# schematics.net
KiCad netlist of a schematic drawn in EAGLE
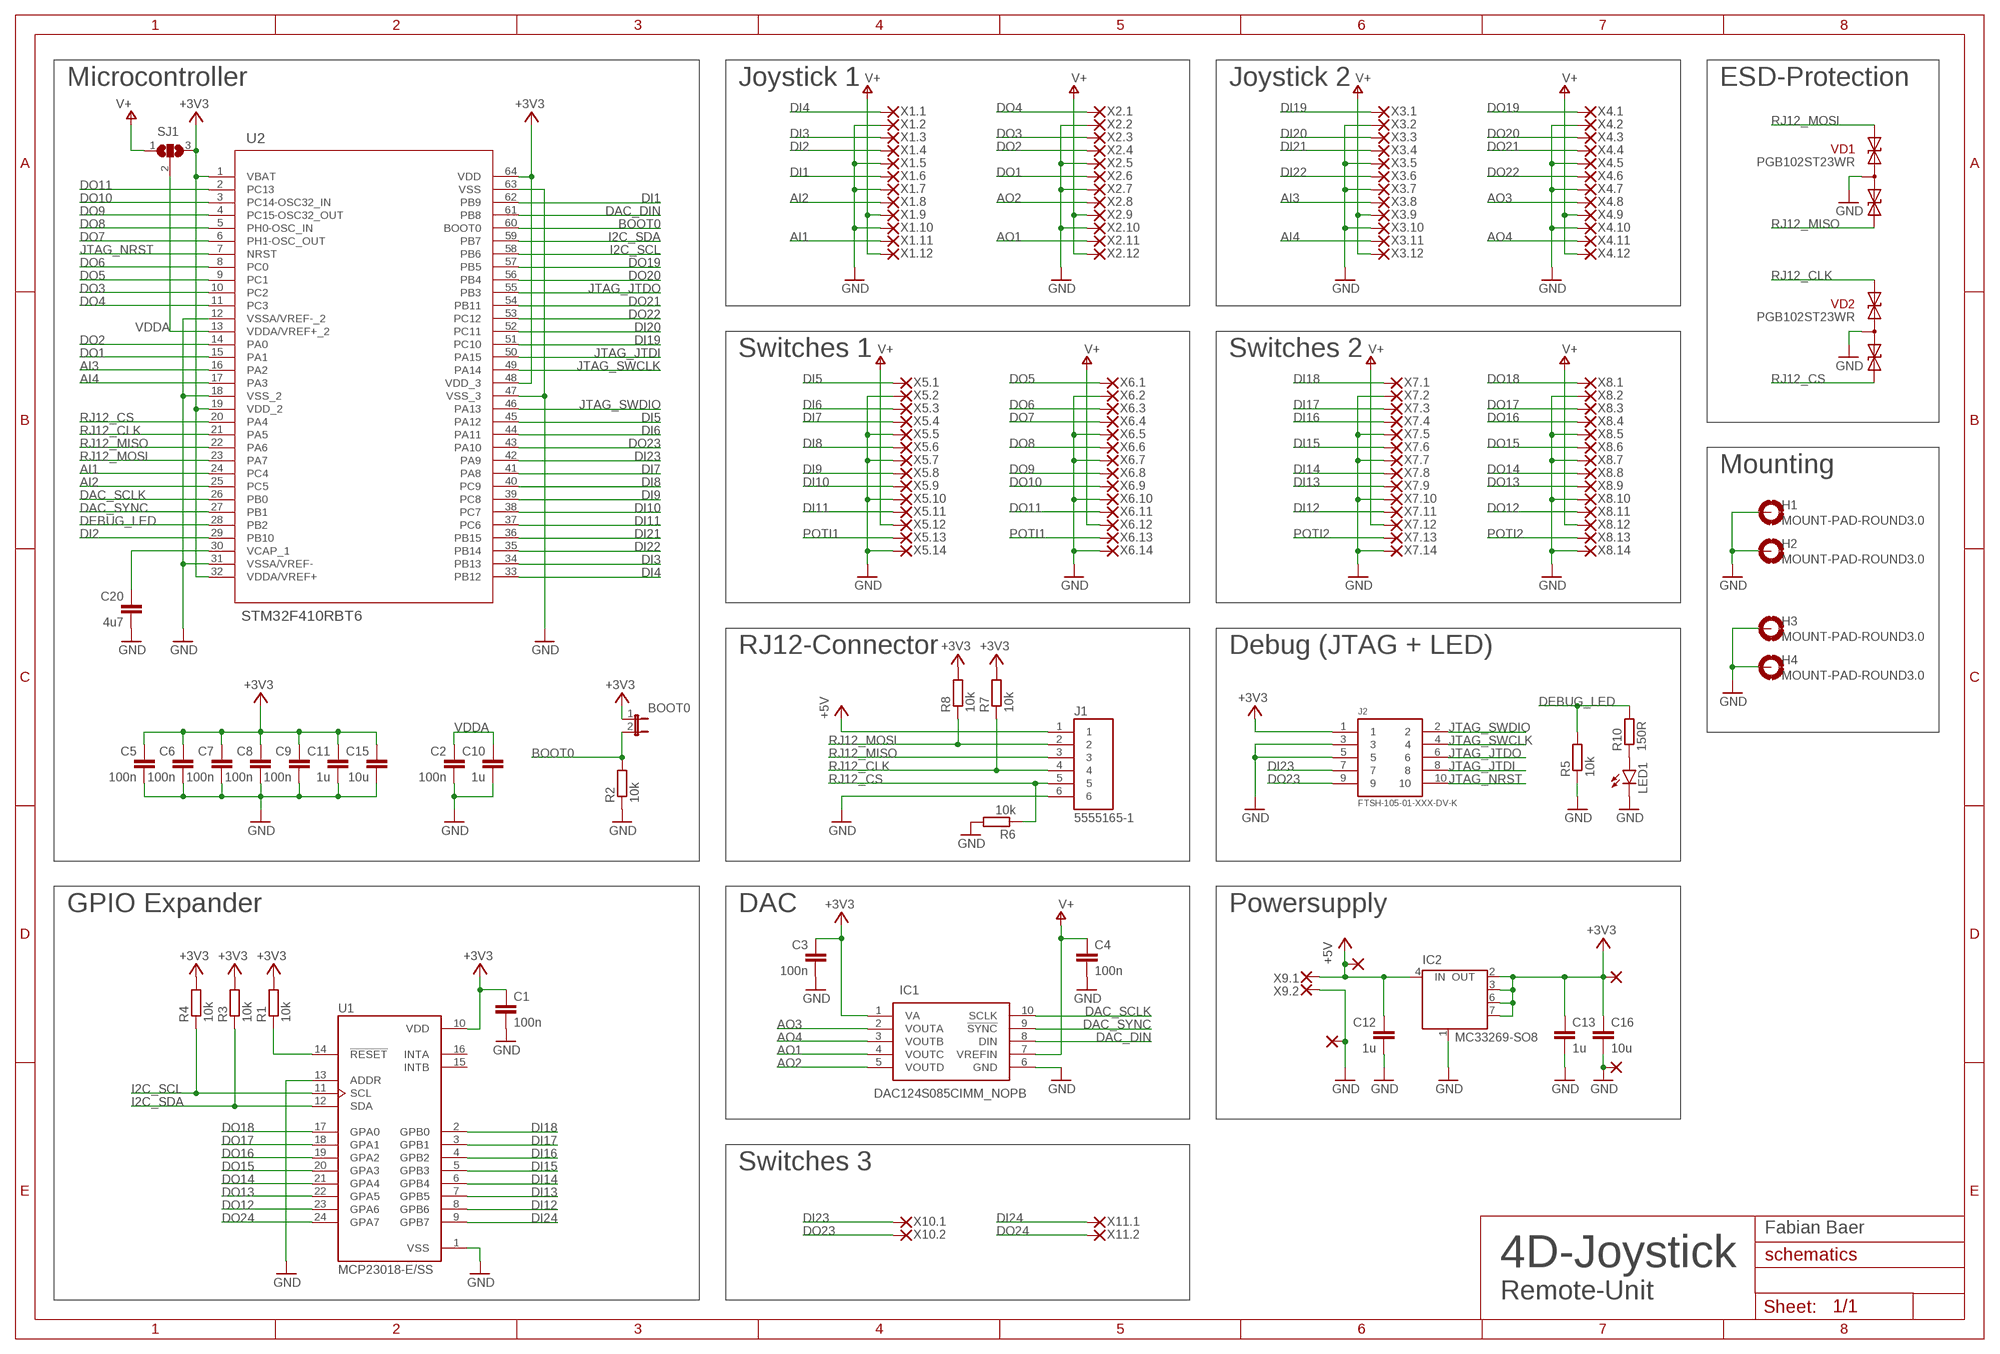
[diagram p0: schematic, sheet 1]

(export (version "E")
  (design (tool "Eeschema 10.0.6"))
  (components
    (comp (ref "BOOT0")
      (value "JP1E")
      (footprint "eagle-import:JP1")
      (libsource (lib "eagle-import") (part "JP1E"))
    )
    (comp (ref "C1")
      (value "100n")
      (footprint "eagle-import:C0603")
      (libsource (lib "eagle-import") (part "C-EUC0603"))
    )
    (comp (ref "C2")
      (value "100n")
      (footprint "eagle-import:C0603")
      (libsource (lib "eagle-import") (part "C-EUC0603"))
    )
    (comp (ref "C3")
      (value "100n")
      (footprint "eagle-import:C0603")
      (libsource (lib "eagle-import") (part "C-EUC0603"))
    )
    (comp (ref "C4")
      (value "100n")
      (footprint "eagle-import:C0603")
      (libsource (lib "eagle-import") (part "C-EUC0603"))
    )
    (comp (ref "C5")
      (value "100n")
      (footprint "eagle-import:C0603")
      (libsource (lib "eagle-import") (part "C-EUC0603"))
    )
    (comp (ref "C6")
      (value "100n")
      (footprint "eagle-import:C0603")
      (libsource (lib "eagle-import") (part "C-EUC0603"))
    )
    (comp (ref "C7")
      (value "100n")
      (footprint "eagle-import:C0603")
      (libsource (lib "eagle-import") (part "C-EUC0603"))
    )
    (comp (ref "C8")
      (value "100n")
      (footprint "eagle-import:C0603")
      (libsource (lib "eagle-import") (part "C-EUC0603"))
    )
    (comp (ref "C9")
      (value "100n")
      (footprint "eagle-import:C0603")
      (libsource (lib "eagle-import") (part "C-EUC0603"))
    )
    (comp (ref "C10")
      (value "1u")
      (footprint "eagle-import:C0603")
      (libsource (lib "eagle-import") (part "C-EUC0603"))
    )
    (comp (ref "C11")
      (value "1u")
      (footprint "eagle-import:C0603")
      (libsource (lib "eagle-import") (part "C-EUC0603"))
    )
    (comp (ref "C12")
      (value "1u")
      (footprint "eagle-import:C0603")
      (libsource (lib "eagle-import") (part "C-EUC0603"))
    )
    (comp (ref "C13")
      (value "1u")
      (footprint "eagle-import:C0603")
      (libsource (lib "eagle-import") (part "C-EUC0603"))
    )
    (comp (ref "C15")
      (value "10u")
      (footprint "eagle-import:C0603")
      (libsource (lib "eagle-import") (part "C-EUC0603"))
    )
    (comp (ref "C16")
      (value "10u")
      (footprint "eagle-import:C0603")
      (libsource (lib "eagle-import") (part "C-EUC0603"))
    )
    (comp (ref "C20")
      (value "4u7")
      (footprint "eagle-import:C0603")
      (libsource (lib "eagle-import") (part "C-EUC0603"))
    )
    (comp (ref "H1")
      (value "MOUNT-PAD-ROUND3.0")
      (footprint "eagle-import:3,0-PAD")
      (libsource (lib "eagle-import") (part "MOUNT-PAD-ROUND3.0"))
    )
    (comp (ref "H2")
      (value "MOUNT-PAD-ROUND3.0")
      (footprint "eagle-import:3,0-PAD")
      (libsource (lib "eagle-import") (part "MOUNT-PAD-ROUND3.0"))
    )
    (comp (ref "H3")
      (value "MOUNT-PAD-ROUND3.0")
      (footprint "eagle-import:3,0-PAD")
      (libsource (lib "eagle-import") (part "MOUNT-PAD-ROUND3.0"))
    )
    (comp (ref "H4")
      (value "MOUNT-PAD-ROUND3.0")
      (footprint "eagle-import:3,0-PAD")
      (libsource (lib "eagle-import") (part "MOUNT-PAD-ROUND3.0"))
    )
    (comp (ref "IC1")
      (value "DAC124S085CIMM_NOPB")
      (footprint "eagle-import:SOP50P490X110-10N")
      (fields
        (field (name "MANUFACTURER_PART_NUMBER") "DAC124S085CIMM/NOPB")
        (field (name "MOUSER_PART_NUMBER") "926-DAC124S085CIMMNO")
        (field (name "RS_PART_NUMBER") "6512026P")
      )
      (libsource (lib "eagle-import") (part "DAC124S085CIMM_NOPB"))
    )
    (comp (ref "IC2")
      (value "MC33269-SO8")
      (footprint "eagle-import:SO08")
      (libsource (lib "eagle-import") (part "MC33269-SO8"))
    )
    (comp (ref "J1")
      (value "5555165-1")
      (footprint "eagle-import:TE_5555165-1")
      (fields (field (name "MF") "TE Connectivity"))
      (libsource (lib "eagle-import") (part "5555165-1"))
    )
    (comp (ref "J2")
      (value "FTSH-105-01-XXX-DV-K")
      (footprint "eagle-import:FTSH-105-01-XXX-DV-K")
      (libsource (lib "eagle-import") (part "FTSH-105-01-XXX-DV-K"))
    )
    (comp (ref "LED1")
      (value "LEDSML0603")
      (footprint "eagle-import:SML0603")
      (libsource (lib "eagle-import") (part "LEDSML0603"))
    )
    (comp (ref "R1")
      (value "10k")
      (footprint "eagle-import:R0603")
      (libsource (lib "eagle-import") (part "R-EU_R0603"))
    )
    (comp (ref "R2")
      (value "10k")
      (footprint "eagle-import:R0603")
      (libsource (lib "eagle-import") (part "R-EU_R0603"))
    )
    (comp (ref "R3")
      (value "10k")
      (footprint "eagle-import:R0603")
      (libsource (lib "eagle-import") (part "R-EU_R0603"))
    )
    (comp (ref "R4")
      (value "10k")
      (footprint "eagle-import:R0603")
      (libsource (lib "eagle-import") (part "R-EU_R0603"))
    )
    (comp (ref "R5")
      (value "10k")
      (footprint "eagle-import:R0603")
      (libsource (lib "eagle-import") (part "R-EU_R0603"))
    )
    (comp (ref "R6")
      (value "10k")
      (footprint "eagle-import:R0603")
      (libsource (lib "eagle-import") (part "R-EU_R0603"))
    )
    (comp (ref "R7")
      (value "10k")
      (footprint "eagle-import:R0603")
      (libsource (lib "eagle-import") (part "R-EU_R0603"))
    )
    (comp (ref "R8")
      (value "10k")
      (footprint "eagle-import:R0603")
      (libsource (lib "eagle-import") (part "R-EU_R0603"))
    )
    (comp (ref "R10")
      (value "150R")
      (footprint "eagle-import:R0603")
      (libsource (lib "eagle-import") (part "R-EU_R0603"))
    )
    (comp (ref "SJ1")
      (value "SJ2W")
      (footprint "eagle-import:SJ_2")
      (libsource (lib "eagle-import") (part "SJ2W"))
    )
    (comp (ref "U1")
      (value "MCP23018-E/SS")
      (footprint "eagle-import:SOP65P780X200-24N")
      (fields (field (name "MF") "Microchip"))
      (libsource (lib "eagle-import") (part "MCP23018-E/SS"))
    )
    (comp (ref "U2")
      (value "STM32F410RBT6")
      (footprint "eagle-import:LQFP64-10X10MM")
      (fields (field (name "MANUFACTURER_PART_NUMBER") "stm32f410r3"))
      (libsource (lib "eagle-import") (part "STM32F410RBT6"))
    )
    (comp (ref "VD1")
      (value "PGB102ST23WR")
      (footprint "eagle-import:SOT23")
      (libsource (lib "eagle-import") (part "PGB102ST23WR"))
    )
    (comp (ref "VD2")
      (value "PGB102ST23WR")
      (footprint "eagle-import:SOT23")
      (libsource (lib "eagle-import") (part "PGB102ST23WR"))
    )
    (comp (ref "X1.1")
      (value "WIREPAD1,6/0,9")
      (footprint "eagle-import:1,6_0,9")
      (libsource (lib "eagle-import") (part "WIREPAD1,6/0,9"))
    )
    (comp (ref "X1.2")
      (value "WIREPAD1,6/0,9")
      (footprint "eagle-import:1,6_0,9")
      (libsource (lib "eagle-import") (part "WIREPAD1,6/0,9"))
    )
    (comp (ref "X1.3")
      (value "WIREPAD1,6/0,9")
      (footprint "eagle-import:1,6_0,9")
      (libsource (lib "eagle-import") (part "WIREPAD1,6/0,9"))
    )
    (comp (ref "X1.4")
      (value "WIREPAD1,6/0,9")
      (footprint "eagle-import:1,6_0,9")
      (libsource (lib "eagle-import") (part "WIREPAD1,6/0,9"))
    )
    (comp (ref "X1.5")
      (value "WIREPAD1,6/0,9")
      (footprint "eagle-import:1,6_0,9")
      (libsource (lib "eagle-import") (part "WIREPAD1,6/0,9"))
    )
    (comp (ref "X1.6")
      (value "WIREPAD1,6/0,9")
      (footprint "eagle-import:1,6_0,9")
      (libsource (lib "eagle-import") (part "WIREPAD1,6/0,9"))
    )
    (comp (ref "X1.7")
      (value "WIREPAD1,6/0,9")
      (footprint "eagle-import:1,6_0,9")
      (libsource (lib "eagle-import") (part "WIREPAD1,6/0,9"))
    )
    (comp (ref "X1.8")
      (value "WIREPAD1,6/0,9")
      (footprint "eagle-import:1,6_0,9")
      (libsource (lib "eagle-import") (part "WIREPAD1,6/0,9"))
    )
    (comp (ref "X1.9")
      (value "WIREPAD1,6/0,9")
      (footprint "eagle-import:1,6_0,9")
      (libsource (lib "eagle-import") (part "WIREPAD1,6/0,9"))
    )
    (comp (ref "X1.10")
      (value "WIREPAD1,6/0,9")
      (footprint "eagle-import:1,6_0,9")
      (libsource (lib "eagle-import") (part "WIREPAD1,6/0,9"))
    )
    (comp (ref "X1.11")
      (value "WIREPAD1,6/0,9")
      (footprint "eagle-import:1,6_0,9")
      (libsource (lib "eagle-import") (part "WIREPAD1,6/0,9"))
    )
    (comp (ref "X1.12")
      (value "WIREPAD1,6/0,9")
      (footprint "eagle-import:1,6_0,9")
      (libsource (lib "eagle-import") (part "WIREPAD1,6/0,9"))
    )
    (comp (ref "X2.1")
      (value "WIREPAD1,6/0,9")
      (footprint "eagle-import:1,6_0,9")
      (libsource (lib "eagle-import") (part "WIREPAD1,6/0,9"))
    )
    (comp (ref "X2.2")
      (value "WIREPAD1,6/0,9")
      (footprint "eagle-import:1,6_0,9")
      (libsource (lib "eagle-import") (part "WIREPAD1,6/0,9"))
    )
    (comp (ref "X2.3")
      (value "WIREPAD1,6/0,9")
      (footprint "eagle-import:1,6_0,9")
      (libsource (lib "eagle-import") (part "WIREPAD1,6/0,9"))
    )
    (comp (ref "X2.4")
      (value "WIREPAD1,6/0,9")
      (footprint "eagle-import:1,6_0,9")
      (libsource (lib "eagle-import") (part "WIREPAD1,6/0,9"))
    )
    (comp (ref "X2.5")
      (value "WIREPAD1,6/0,9")
      (footprint "eagle-import:1,6_0,9")
      (libsource (lib "eagle-import") (part "WIREPAD1,6/0,9"))
    )
    (comp (ref "X2.6")
      (value "WIREPAD1,6/0,9")
      (footprint "eagle-import:1,6_0,9")
      (libsource (lib "eagle-import") (part "WIREPAD1,6/0,9"))
    )
    (comp (ref "X2.7")
      (value "WIREPAD1,6/0,9")
      (footprint "eagle-import:1,6_0,9")
      (libsource (lib "eagle-import") (part "WIREPAD1,6/0,9"))
    )
    (comp (ref "X2.8")
      (value "WIREPAD1,6/0,9")
      (footprint "eagle-import:1,6_0,9")
      (libsource (lib "eagle-import") (part "WIREPAD1,6/0,9"))
    )
    (comp (ref "X2.9")
      (value "WIREPAD1,6/0,9")
      (footprint "eagle-import:1,6_0,9")
      (libsource (lib "eagle-import") (part "WIREPAD1,6/0,9"))
    )
    (comp (ref "X2.10")
      (value "WIREPAD1,6/0,9")
      (footprint "eagle-import:1,6_0,9")
      (libsource (lib "eagle-import") (part "WIREPAD1,6/0,9"))
    )
    (comp (ref "X2.11")
      (value "WIREPAD1,6/0,9")
      (footprint "eagle-import:1,6_0,9")
      (libsource (lib "eagle-import") (part "WIREPAD1,6/0,9"))
    )
    (comp (ref "X2.12")
      (value "WIREPAD1,6/0,9")
      (footprint "eagle-import:1,6_0,9")
      (libsource (lib "eagle-import") (part "WIREPAD1,6/0,9"))
    )
    (comp (ref "X3.1")
      (value "WIREPAD1,6/0,9")
      (footprint "eagle-import:1,6_0,9")
      (libsource (lib "eagle-import") (part "WIREPAD1,6/0,9"))
    )
    (comp (ref "X3.2")
      (value "WIREPAD1,6/0,9")
      (footprint "eagle-import:1,6_0,9")
      (libsource (lib "eagle-import") (part "WIREPAD1,6/0,9"))
    )
    (comp (ref "X3.3")
      (value "WIREPAD1,6/0,9")
      (footprint "eagle-import:1,6_0,9")
      (libsource (lib "eagle-import") (part "WIREPAD1,6/0,9"))
    )
    (comp (ref "X3.4")
      (value "WIREPAD1,6/0,9")
      (footprint "eagle-import:1,6_0,9")
      (libsource (lib "eagle-import") (part "WIREPAD1,6/0,9"))
    )
    (comp (ref "X3.5")
      (value "WIREPAD1,6/0,9")
      (footprint "eagle-import:1,6_0,9")
      (libsource (lib "eagle-import") (part "WIREPAD1,6/0,9"))
    )
    (comp (ref "X3.6")
      (value "WIREPAD1,6/0,9")
      (footprint "eagle-import:1,6_0,9")
      (libsource (lib "eagle-import") (part "WIREPAD1,6/0,9"))
    )
    (comp (ref "X3.7")
      (value "WIREPAD1,6/0,9")
      (footprint "eagle-import:1,6_0,9")
      (libsource (lib "eagle-import") (part "WIREPAD1,6/0,9"))
    )
    (comp (ref "X3.8")
      (value "WIREPAD1,6/0,9")
      (footprint "eagle-import:1,6_0,9")
      (libsource (lib "eagle-import") (part "WIREPAD1,6/0,9"))
    )
    (comp (ref "X3.9")
      (value "WIREPAD1,6/0,9")
      (footprint "eagle-import:1,6_0,9")
      (libsource (lib "eagle-import") (part "WIREPAD1,6/0,9"))
    )
    (comp (ref "X3.10")
      (value "WIREPAD1,6/0,9")
      (footprint "eagle-import:1,6_0,9")
      (libsource (lib "eagle-import") (part "WIREPAD1,6/0,9"))
    )
    (comp (ref "X3.11")
      (value "WIREPAD1,6/0,9")
      (footprint "eagle-import:1,6_0,9")
      (libsource (lib "eagle-import") (part "WIREPAD1,6/0,9"))
    )
    (comp (ref "X3.12")
      (value "WIREPAD1,6/0,9")
      (footprint "eagle-import:1,6_0,9")
      (libsource (lib "eagle-import") (part "WIREPAD1,6/0,9"))
    )
    (comp (ref "X4.1")
      (value "WIREPAD1,6/0,9")
      (footprint "eagle-import:1,6_0,9")
      (libsource (lib "eagle-import") (part "WIREPAD1,6/0,9"))
    )
    (comp (ref "X4.2")
      (value "WIREPAD1,6/0,9")
      (footprint "eagle-import:1,6_0,9")
      (libsource (lib "eagle-import") (part "WIREPAD1,6/0,9"))
    )
    (comp (ref "X4.3")
      (value "WIREPAD1,6/0,9")
      (footprint "eagle-import:1,6_0,9")
      (libsource (lib "eagle-import") (part "WIREPAD1,6/0,9"))
    )
    (comp (ref "X4.4")
      (value "WIREPAD1,6/0,9")
      (footprint "eagle-import:1,6_0,9")
      (libsource (lib "eagle-import") (part "WIREPAD1,6/0,9"))
    )
    (comp (ref "X4.5")
      (value "WIREPAD1,6/0,9")
      (footprint "eagle-import:1,6_0,9")
      (libsource (lib "eagle-import") (part "WIREPAD1,6/0,9"))
    )
    (comp (ref "X4.6")
      (value "WIREPAD1,6/0,9")
      (footprint "eagle-import:1,6_0,9")
      (libsource (lib "eagle-import") (part "WIREPAD1,6/0,9"))
    )
    (comp (ref "X4.7")
      (value "WIREPAD1,6/0,9")
      (footprint "eagle-import:1,6_0,9")
      (libsource (lib "eagle-import") (part "WIREPAD1,6/0,9"))
    )
    (comp (ref "X4.8")
      (value "WIREPAD1,6/0,9")
      (footprint "eagle-import:1,6_0,9")
      (libsource (lib "eagle-import") (part "WIREPAD1,6/0,9"))
    )
    (comp (ref "X4.9")
      (value "WIREPAD1,6/0,9")
      (footprint "eagle-import:1,6_0,9")
      (libsource (lib "eagle-import") (part "WIREPAD1,6/0,9"))
    )
    (comp (ref "X4.10")
      (value "WIREPAD1,6/0,9")
      (footprint "eagle-import:1,6_0,9")
      (libsource (lib "eagle-import") (part "WIREPAD1,6/0,9"))
    )
    (comp (ref "X4.11")
      (value "WIREPAD1,6/0,9")
      (footprint "eagle-import:1,6_0,9")
      (libsource (lib "eagle-import") (part "WIREPAD1,6/0,9"))
    )
    (comp (ref "X4.12")
      (value "WIREPAD1,6/0,9")
      (footprint "eagle-import:1,6_0,9")
      (libsource (lib "eagle-import") (part "WIREPAD1,6/0,9"))
    )
    (comp (ref "X5.1")
      (value "WIREPAD1,6/0,9")
      (footprint "eagle-import:1,6_0,9")
      (libsource (lib "eagle-import") (part "WIREPAD1,6/0,9"))
    )
    (comp (ref "X5.2")
      (value "WIREPAD1,6/0,9")
      (footprint "eagle-import:1,6_0,9")
      (libsource (lib "eagle-import") (part "WIREPAD1,6/0,9"))
    )
    (comp (ref "X5.3")
      (value "WIREPAD1,6/0,9")
      (footprint "eagle-import:1,6_0,9")
      (libsource (lib "eagle-import") (part "WIREPAD1,6/0,9"))
    )
    (comp (ref "X5.4")
      (value "WIREPAD1,6/0,9")
      (footprint "eagle-import:1,6_0,9")
      (libsource (lib "eagle-import") (part "WIREPAD1,6/0,9"))
    )
    (comp (ref "X5.5")
      (value "WIREPAD1,6/0,9")
      (footprint "eagle-import:1,6_0,9")
      (libsource (lib "eagle-import") (part "WIREPAD1,6/0,9"))
    )
    (comp (ref "X5.6")
      (value "WIREPAD1,6/0,9")
      (footprint "eagle-import:1,6_0,9")
      (libsource (lib "eagle-import") (part "WIREPAD1,6/0,9"))
    )
    (comp (ref "X5.7")
      (value "WIREPAD1,6/0,9")
      (footprint "eagle-import:1,6_0,9")
      (libsource (lib "eagle-import") (part "WIREPAD1,6/0,9"))
    )
    (comp (ref "X5.8")
      (value "WIREPAD1,6/0,9")
      (footprint "eagle-import:1,6_0,9")
      (libsource (lib "eagle-import") (part "WIREPAD1,6/0,9"))
    )
    (comp (ref "X5.9")
      (value "WIREPAD1,6/0,9")
      (footprint "eagle-import:1,6_0,9")
      (libsource (lib "eagle-import") (part "WIREPAD1,6/0,9"))
    )
    (comp (ref "X5.10")
      (value "WIREPAD1,6/0,9")
      (footprint "eagle-import:1,6_0,9")
      (libsource (lib "eagle-import") (part "WIREPAD1,6/0,9"))
    )
    (comp (ref "X5.11")
      (value "WIREPAD1,6/0,9")
      (footprint "eagle-import:1,6_0,9")
      (libsource (lib "eagle-import") (part "WIREPAD1,6/0,9"))
    )
    (comp (ref "X5.12")
      (value "WIREPAD1,6/0,9")
      (footprint "eagle-import:1,6_0,9")
      (libsource (lib "eagle-import") (part "WIREPAD1,6/0,9"))
    )
    (comp (ref "X5.13")
      (value "WIREPAD1,6/0,9")
      (footprint "eagle-import:1,6_0,9")
      (libsource (lib "eagle-import") (part "WIREPAD1,6/0,9"))
    )
    (comp (ref "X5.14")
      (value "WIREPAD1,6/0,9")
      (footprint "eagle-import:1,6_0,9")
      (libsource (lib "eagle-import") (part "WIREPAD1,6/0,9"))
    )
    (comp (ref "X5.15")
      (value "WIREPAD1,6/0,9")
      (footprint "eagle-import:1,6_0,9")
      (libsource (lib "eagle-import") (part "WIREPAD1,6/0,9"))
    )
    (comp (ref "X5.16")
      (value "WIREPAD1,6/0,9")
      (footprint "eagle-import:1,6_0,9")
      (libsource (lib "eagle-import") (part "WIREPAD1,6/0,9"))
    )
    (comp (ref "X5.17")
      (value "WIREPAD1,6/0,9")
      (footprint "eagle-import:1,6_0,9")
      (libsource (lib "eagle-import") (part "WIREPAD1,6/0,9"))
    )
    (comp (ref "X5.18")
      (value "WIREPAD1,6/0,9")
      (footprint "eagle-import:1,6_0,9")
      (libsource (lib "eagle-import") (part "WIREPAD1,6/0,9"))
    )
    (comp (ref "X6.1")
      (value "WIREPAD1,6/0,9")
      (footprint "eagle-import:1,6_0,9")
      (libsource (lib "eagle-import") (part "WIREPAD1,6/0,9"))
    )
    (comp (ref "X6.2")
      (value "WIREPAD1,6/0,9")
      (footprint "eagle-import:1,6_0,9")
      (libsource (lib "eagle-import") (part "WIREPAD1,6/0,9"))
    )
    (comp (ref "X6.3")
      (value "WIREPAD1,6/0,9")
      (footprint "eagle-import:1,6_0,9")
      (libsource (lib "eagle-import") (part "WIREPAD1,6/0,9"))
    )
    (comp (ref "X6.4")
      (value "WIREPAD1,6/0,9")
      (footprint "eagle-import:1,6_0,9")
      (libsource (lib "eagle-import") (part "WIREPAD1,6/0,9"))
    )
    (comp (ref "X6.5")
      (value "WIREPAD1,6/0,9")
      (footprint "eagle-import:1,6_0,9")
      (libsource (lib "eagle-import") (part "WIREPAD1,6/0,9"))
    )
    (comp (ref "X6.6")
      (value "WIREPAD1,6/0,9")
      (footprint "eagle-import:1,6_0,9")
      (libsource (lib "eagle-import") (part "WIREPAD1,6/0,9"))
    )
    (comp (ref "X6.7")
      (value "WIREPAD1,6/0,9")
      (footprint "eagle-import:1,6_0,9")
      (libsource (lib "eagle-import") (part "WIREPAD1,6/0,9"))
    )
    (comp (ref "X6.8")
      (value "WIREPAD1,6/0,9")
      (footprint "eagle-import:1,6_0,9")
      (libsource (lib "eagle-import") (part "WIREPAD1,6/0,9"))
    )
    (comp (ref "X6.9")
      (value "WIREPAD1,6/0,9")
      (footprint "eagle-import:1,6_0,9")
      (libsource (lib "eagle-import") (part "WIREPAD1,6/0,9"))
    )
    (comp (ref "X6.10")
      (value "WIREPAD1,6/0,9")
      (footprint "eagle-import:1,6_0,9")
      (libsource (lib "eagle-import") (part "WIREPAD1,6/0,9"))
    )
    (comp (ref "X6.11")
      (value "WIREPAD1,6/0,9")
      (footprint "eagle-import:1,6_0,9")
      (libsource (lib "eagle-import") (part "WIREPAD1,6/0,9"))
    )
    (comp (ref "X6.12")
      (value "WIREPAD1,6/0,9")
      (footprint "eagle-import:1,6_0,9")
      (libsource (lib "eagle-import") (part "WIREPAD1,6/0,9"))
    )
    (comp (ref "X6.13")
      (value "WIREPAD1,6/0,9")
      (footprint "eagle-import:1,6_0,9")
      (libsource (lib "eagle-import") (part "WIREPAD1,6/0,9"))
    )
    (comp (ref "X6.14")
      (value "WIREPAD1,6/0,9")
      (footprint "eagle-import:1,6_0,9")
      (libsource (lib "eagle-import") (part "WIREPAD1,6/0,9"))
    )
    (comp (ref "X7.1")
      (value "WIREPAD1,6/0,9")
      (footprint "eagle-import:1,6_0,9")
      (libsource (lib "eagle-import") (part "WIREPAD1,6/0,9"))
    )
    (comp (ref "X7.2")
      (value "WIREPAD1,6/0,9")
      (footprint "eagle-import:1,6_0,9")
      (libsource (lib "eagle-import") (part "WIREPAD1,6/0,9"))
    )
    (comp (ref "X7.3")
      (value "WIREPAD1,6/0,9")
      (footprint "eagle-import:1,6_0,9")
      (libsource (lib "eagle-import") (part "WIREPAD1,6/0,9"))
    )
    (comp (ref "X7.4")
      (value "WIREPAD1,6/0,9")
      (footprint "eagle-import:1,6_0,9")
      (libsource (lib "eagle-import") (part "WIREPAD1,6/0,9"))
    )
    (comp (ref "X7.5")
      (value "WIREPAD1,6/0,9")
      (footprint "eagle-import:1,6_0,9")
      (libsource (lib "eagle-import") (part "WIREPAD1,6/0,9"))
    )
    (comp (ref "X7.6")
      (value "WIREPAD1,6/0,9")
      (footprint "eagle-import:1,6_0,9")
      (libsource (lib "eagle-import") (part "WIREPAD1,6/0,9"))
    )
    (comp (ref "X7.7")
      (value "WIREPAD1,6/0,9")
      (footprint "eagle-import:1,6_0,9")
      (libsource (lib "eagle-import") (part "WIREPAD1,6/0,9"))
    )
    (comp (ref "X7.8")
      (value "WIREPAD1,6/0,9")
      (footprint "eagle-import:1,6_0,9")
      (libsource (lib "eagle-import") (part "WIREPAD1,6/0,9"))
    )
    (comp (ref "X7.9")
      (value "WIREPAD1,6/0,9")
      (footprint "eagle-import:1,6_0,9")
      (libsource (lib "eagle-import") (part "WIREPAD1,6/0,9"))
    )
    (comp (ref "X7.10")
      (value "WIREPAD1,6/0,9")
      (footprint "eagle-import:1,6_0,9")
      (libsource (lib "eagle-import") (part "WIREPAD1,6/0,9"))
    )
    (comp (ref "X7.11")
      (value "WIREPAD1,6/0,9")
      (footprint "eagle-import:1,6_0,9")
      (libsource (lib "eagle-import") (part "WIREPAD1,6/0,9"))
    )
    (comp (ref "X7.12")
      (value "WIREPAD1,6/0,9")
      (footprint "eagle-import:1,6_0,9")
      (libsource (lib "eagle-import") (part "WIREPAD1,6/0,9"))
    )
    (comp (ref "X7.13")
      (value "WIREPAD1,6/0,9")
      (footprint "eagle-import:1,6_0,9")
      (libsource (lib "eagle-import") (part "WIREPAD1,6/0,9"))
    )
    (comp (ref "X7.14")
      (value "WIREPAD1,6/0,9")
      (footprint "eagle-import:1,6_0,9")
      (libsource (lib "eagle-import") (part "WIREPAD1,6/0,9"))
    )
    (comp (ref "X8.1")
      (value "WIREPAD1,6/0,9")
      (footprint "eagle-import:1,6_0,9")
      (libsource (lib "eagle-import") (part "WIREPAD1,6/0,9"))
    )
    (comp (ref "X8.2")
      (value "WIREPAD1,6/0,9")
      (footprint "eagle-import:1,6_0,9")
      (libsource (lib "eagle-import") (part "WIREPAD1,6/0,9"))
    )
    (comp (ref "X8.3")
      (value "WIREPAD1,6/0,9")
      (footprint "eagle-import:1,6_0,9")
      (libsource (lib "eagle-import") (part "WIREPAD1,6/0,9"))
    )
    (comp (ref "X8.4")
      (value "WIREPAD1,6/0,9")
      (footprint "eagle-import:1,6_0,9")
      (libsource (lib "eagle-import") (part "WIREPAD1,6/0,9"))
    )
    (comp (ref "X8.5")
      (value "WIREPAD1,6/0,9")
      (footprint "eagle-import:1,6_0,9")
      (libsource (lib "eagle-import") (part "WIREPAD1,6/0,9"))
    )
    (comp (ref "X8.6")
      (value "WIREPAD1,6/0,9")
      (footprint "eagle-import:1,6_0,9")
      (libsource (lib "eagle-import") (part "WIREPAD1,6/0,9"))
    )
    (comp (ref "X8.7")
      (value "WIREPAD1,6/0,9")
      (footprint "eagle-import:1,6_0,9")
      (libsource (lib "eagle-import") (part "WIREPAD1,6/0,9"))
    )
    (comp (ref "X8.8")
      (value "WIREPAD1,6/0,9")
      (footprint "eagle-import:1,6_0,9")
      (libsource (lib "eagle-import") (part "WIREPAD1,6/0,9"))
    )
    (comp (ref "X8.9")
      (value "WIREPAD1,6/0,9")
      (footprint "eagle-import:1,6_0,9")
      (libsource (lib "eagle-import") (part "WIREPAD1,6/0,9"))
    )
    (comp (ref "X8.10")
      (value "WIREPAD1,6/0,9")
      (footprint "eagle-import:1,6_0,9")
      (libsource (lib "eagle-import") (part "WIREPAD1,6/0,9"))
    )
    (comp (ref "X8.11")
      (value "WIREPAD1,6/0,9")
      (footprint "eagle-import:1,6_0,9")
      (libsource (lib "eagle-import") (part "WIREPAD1,6/0,9"))
    )
    (comp (ref "X8.12")
      (value "WIREPAD1,6/0,9")
      (footprint "eagle-import:1,6_0,9")
      (libsource (lib "eagle-import") (part "WIREPAD1,6/0,9"))
    )
    (comp (ref "X8.13")
      (value "WIREPAD1,6/0,9")
      (footprint "eagle-import:1,6_0,9")
      (libsource (lib "eagle-import") (part "WIREPAD1,6/0,9"))
    )
    (comp (ref "X8.14")
      (value "WIREPAD1,6/0,9")
      (footprint "eagle-import:1,6_0,9")
      (libsource (lib "eagle-import") (part "WIREPAD1,6/0,9"))
    )
    (comp (ref "X9.1")
      (value "WIREPAD2,54/1,0")
      (footprint "eagle-import:2,54_1,0")
      (libsource (lib "eagle-import") (part "WIREPAD2,54/1,0"))
    )
    (comp (ref "X9.2")
      (value "WIREPAD2,54/1,0")
      (footprint "eagle-import:2,54_1,0")
      (libsource (lib "eagle-import") (part "WIREPAD2,54/1,0"))
    )
    (comp (ref "X10.1")
      (value "WIREPAD1,6/0,9")
      (footprint "eagle-import:1,6_0,9")
      (libsource (lib "eagle-import") (part "WIREPAD1,6/0,9"))
    )
    (comp (ref "X10.2")
      (value "WIREPAD1,6/0,9")
      (footprint "eagle-import:1,6_0,9")
      (libsource (lib "eagle-import") (part "WIREPAD1,6/0,9"))
    )
    (comp (ref "X11.1")
      (value "WIREPAD1,6/0,9")
      (footprint "eagle-import:1,6_0,9")
      (libsource (lib "eagle-import") (part "WIREPAD1,6/0,9"))
    )
    (comp (ref "X11.2")
      (value "WIREPAD1,6/0,9")
      (footprint "eagle-import:1,6_0,9")
      (libsource (lib "eagle-import") (part "WIREPAD1,6/0,9"))
    )
  )
  (nets
    (net (code "1") (name "+3V3") (class "Default")
      (node (ref "BOOT0") (pin "1") (pinfunction "1_1") (pintype "passive"))
      (node (ref "C1") (pin "1") (pinfunction "1_1") (pintype "passive"))
      (node (ref "C11") (pin "1") (pinfunction "1_1") (pintype "passive"))
      (node (ref "C13") (pin "1") (pinfunction "1_1") (pintype "passive"))
      (node (ref "C15") (pin "1") (pinfunction "1_1") (pintype "passive"))
      (node (ref "C16") (pin "1") (pinfunction "1_1") (pintype "passive"))
      (node (ref "C3") (pin "1") (pinfunction "1_1") (pintype "passive"))
      (node (ref "C5") (pin "1") (pinfunction "1_1") (pintype "passive"))
      (node (ref "C6") (pin "1") (pinfunction "1_1") (pintype "passive"))
      (node (ref "C7") (pin "1") (pinfunction "1_1") (pintype "passive"))
      (node (ref "C8") (pin "1") (pinfunction "1_1") (pintype "passive"))
      (node (ref "C9") (pin "1") (pinfunction "1_1") (pintype "passive"))
      (node (ref "IC1") (pin "1") (pinfunction "VA_1") (pintype "bidirectional"))
      (node (ref "IC2") (pin "2") (pinfunction "OUT_2") (pintype "passive"))
      (node (ref "IC2") (pin "3") (pinfunction "OUT_3") (pintype "passive"))
      (node (ref "IC2") (pin "6") (pinfunction "OUT_6") (pintype "passive"))
      (node (ref "IC2") (pin "7") (pinfunction "OUT_7") (pintype "passive"))
      (node (ref "J2") (pin "1") (pinfunction "1_1") (pintype "bidirectional"))
      (node (ref "R1") (pin "2") (pinfunction "2_2") (pintype "passive"))
      (node (ref "R3") (pin "2") (pinfunction "2_2") (pintype "passive"))
      (node (ref "R4") (pin "2") (pinfunction "2_2") (pintype "passive"))
      (node (ref "R7") (pin "2") (pinfunction "2_2") (pintype "passive"))
      (node (ref "R8") (pin "2") (pinfunction "2_2") (pintype "passive"))
      (node (ref "SJ1") (pin "3") (pinfunction "3_3") (pintype "passive"))
      (node (ref "U1") (pin "10") (pinfunction "VDD_10") (pintype "power_in"))
      (node (ref "U2") (pin "1") (pinfunction "VBAT_1") (pintype "power_in"))
      (node (ref "U2") (pin "19") (pinfunction "VDD_2_19") (pintype "power_in"))
      (node (ref "U2") (pin "32") (pinfunction "VDDA/VREF+_32") (pintype "power_in"))
      (node (ref "U2") (pin "48") (pinfunction "VDD_3_48") (pintype "power_in"))
      (node (ref "U2") (pin "64") (pinfunction "VDD_64") (pintype "power_in"))
      (node (ref "X5.15") (pin "1") (pinfunction "P_1") (pintype "passive"))
    )
    (net (code "2") (name "+5V") (class "Default")
      (node (ref "C12") (pin "1") (pinfunction "1_1") (pintype "passive"))
      (node (ref "IC2") (pin "4") (pinfunction "IN_4") (pintype "input"))
      (node (ref "J1") (pin "1") (pinfunction "1_1") (pintype "passive"))
      (node (ref "X5.17") (pin "1") (pinfunction "P_1") (pintype "passive"))
      (node (ref "X9.1") (pin "1") (pinfunction "P_1") (pintype "passive"))
    )
    (net (code "3") (name "/AI1") (class "Default")
      (node (ref "U2") (pin "24") (pinfunction "PC4_24") (pintype "passive"))
      (node (ref "X1.11") (pin "1") (pinfunction "P_1") (pintype "passive"))
    )
    (net (code "4") (name "/AI2") (class "Default")
      (node (ref "U2") (pin "25") (pinfunction "PC5_25") (pintype "passive"))
      (node (ref "X1.8") (pin "1") (pinfunction "P_1") (pintype "passive"))
    )
    (net (code "5") (name "/AI3") (class "Default")
      (node (ref "U2") (pin "16") (pinfunction "PA2_16") (pintype "passive"))
      (node (ref "X3.8") (pin "1") (pinfunction "P_1") (pintype "passive"))
    )
    (net (code "6") (name "/AI4") (class "Default")
      (node (ref "U2") (pin "17") (pinfunction "PA3_17") (pintype "passive"))
      (node (ref "X3.11") (pin "1") (pinfunction "P_1") (pintype "passive"))
    )
    (net (code "7") (name "/AO1") (class "Default")
      (node (ref "IC1") (pin "4") (pinfunction "VOUTC_4") (pintype "bidirectional"))
      (node (ref "X2.11") (pin "1") (pinfunction "P_1") (pintype "passive"))
    )
    (net (code "8") (name "/AO2") (class "Default")
      (node (ref "IC1") (pin "5") (pinfunction "VOUTD_5") (pintype "bidirectional"))
      (node (ref "X2.8") (pin "1") (pinfunction "P_1") (pintype "passive"))
    )
    (net (code "9") (name "/AO3") (class "Default")
      (node (ref "IC1") (pin "2") (pinfunction "VOUTA_2") (pintype "bidirectional"))
      (node (ref "X4.8") (pin "1") (pinfunction "P_1") (pintype "passive"))
    )
    (net (code "10") (name "/AO4") (class "Default")
      (node (ref "IC1") (pin "3") (pinfunction "VOUTB_3") (pintype "bidirectional"))
      (node (ref "X4.11") (pin "1") (pinfunction "P_1") (pintype "passive"))
    )
    (net (code "11") (name "/BOOT0") (class "Default")
      (node (ref "BOOT0") (pin "2") (pinfunction "2_2") (pintype "passive"))
      (node (ref "R2") (pin "2") (pinfunction "2_2") (pintype "passive"))
      (node (ref "U2") (pin "60") (pinfunction "BOOT0_60") (pintype "input"))
    )
    (net (code "12") (name "/DAC_DIN") (class "Default")
      (node (ref "IC1") (pin "8") (pinfunction "DIN_8") (pintype "bidirectional"))
      (node (ref "U2") (pin "61") (pinfunction "PB8_61") (pintype "passive"))
    )
    (net (code "13") (name "/DAC_SCLK") (class "Default")
      (node (ref "IC1") (pin "10") (pinfunction "SCLK_10") (pintype "bidirectional"))
      (node (ref "U2") (pin "26") (pinfunction "PB0_26") (pintype "passive"))
    )
    (net (code "14") (name "/DAC_SYNC") (class "Default")
      (node (ref "IC1") (pin "9") (pinfunction "~{SYNC}_9") (pintype "bidirectional"))
      (node (ref "U2") (pin "27") (pinfunction "PB1_27") (pintype "passive"))
    )
    (net (code "15") (name "/DEBUG_LED") (class "Default")
      (node (ref "R10") (pin "2") (pinfunction "2_2") (pintype "passive"))
      (node (ref "R5") (pin "2") (pinfunction "2_2") (pintype "passive"))
      (node (ref "U2") (pin "28") (pinfunction "PB2_28") (pintype "passive"))
    )
    (net (code "16") (name "/DI1") (class "Default")
      (node (ref "U2") (pin "62") (pinfunction "PB9_62") (pintype "passive"))
      (node (ref "X1.6") (pin "1") (pinfunction "P_1") (pintype "passive"))
    )
    (net (code "17") (name "/DI2") (class "Default")
      (node (ref "U2") (pin "29") (pinfunction "PB10_29") (pintype "passive"))
      (node (ref "X1.4") (pin "1") (pinfunction "P_1") (pintype "passive"))
    )
    (net (code "18") (name "/DI3") (class "Default")
      (node (ref "U2") (pin "34") (pinfunction "PB13_34") (pintype "passive"))
      (node (ref "X1.3") (pin "1") (pinfunction "P_1") (pintype "passive"))
    )
    (net (code "19") (name "/DI4") (class "Default")
      (node (ref "U2") (pin "33") (pinfunction "PB12_33") (pintype "passive"))
      (node (ref "X1.1") (pin "1") (pinfunction "P_1") (pintype "passive"))
    )
    (net (code "20") (name "/DI5") (class "Default")
      (node (ref "U2") (pin "45") (pinfunction "PA12_45") (pintype "passive"))
      (node (ref "X5.1") (pin "1") (pinfunction "P_1") (pintype "passive"))
    )
    (net (code "21") (name "/DI6") (class "Default")
      (node (ref "U2") (pin "44") (pinfunction "PA11_44") (pintype "passive"))
      (node (ref "X5.3") (pin "1") (pinfunction "P_1") (pintype "passive"))
    )
    (net (code "22") (name "/DI7") (class "Default")
      (node (ref "U2") (pin "41") (pinfunction "PA8_41") (pintype "passive"))
      (node (ref "X5.4") (pin "1") (pinfunction "P_1") (pintype "passive"))
    )
    (net (code "23") (name "/DI8") (class "Default")
      (node (ref "U2") (pin "40") (pinfunction "PC9_40") (pintype "passive"))
      (node (ref "X5.6") (pin "1") (pinfunction "P_1") (pintype "passive"))
    )
    (net (code "24") (name "/DI9") (class "Default")
      (node (ref "U2") (pin "39") (pinfunction "PC8_39") (pintype "passive"))
      (node (ref "X5.8") (pin "1") (pinfunction "P_1") (pintype "passive"))
    )
    (net (code "25") (name "/DI10") (class "Default")
      (node (ref "U2") (pin "38") (pinfunction "PC7_38") (pintype "passive"))
      (node (ref "X5.9") (pin "1") (pinfunction "P_1") (pintype "passive"))
    )
    (net (code "26") (name "/DI11") (class "Default")
      (node (ref "U2") (pin "37") (pinfunction "PC6_37") (pintype "passive"))
      (node (ref "X5.11") (pin "1") (pinfunction "P_1") (pintype "passive"))
    )
    (net (code "27") (name "/DI12") (class "Default")
      (node (ref "U1") (pin "8") (pinfunction "GPB6_8") (pintype "bidirectional"))
      (node (ref "X7.11") (pin "1") (pinfunction "P_1") (pintype "passive"))
    )
    (net (code "28") (name "/DI13") (class "Default")
      (node (ref "U1") (pin "7") (pinfunction "GPB5_7") (pintype "bidirectional"))
      (node (ref "X7.9") (pin "1") (pinfunction "P_1") (pintype "passive"))
    )
    (net (code "29") (name "/DI14") (class "Default")
      (node (ref "U1") (pin "6") (pinfunction "GPB4_6") (pintype "bidirectional"))
      (node (ref "X7.8") (pin "1") (pinfunction "P_1") (pintype "passive"))
    )
    (net (code "30") (name "/DI15") (class "Default")
      (node (ref "U1") (pin "5") (pinfunction "GPB3_5") (pintype "bidirectional"))
      (node (ref "X7.6") (pin "1") (pinfunction "P_1") (pintype "passive"))
    )
    (net (code "31") (name "/DI16") (class "Default")
      (node (ref "U1") (pin "4") (pinfunction "GPB2_4") (pintype "bidirectional"))
      (node (ref "X7.4") (pin "1") (pinfunction "P_1") (pintype "passive"))
    )
    (net (code "32") (name "/DI17") (class "Default")
      (node (ref "U1") (pin "3") (pinfunction "GPB1_3") (pintype "bidirectional"))
      (node (ref "X7.3") (pin "1") (pinfunction "P_1") (pintype "passive"))
    )
    (net (code "33") (name "/DI18") (class "Default")
      (node (ref "U1") (pin "2") (pinfunction "GPB0_2") (pintype "bidirectional"))
      (node (ref "X7.1") (pin "1") (pinfunction "P_1") (pintype "passive"))
    )
    (net (code "34") (name "/DI19") (class "Default")
      (node (ref "U2") (pin "51") (pinfunction "PC10_51") (pintype "passive"))
      (node (ref "X3.1") (pin "1") (pinfunction "P_1") (pintype "passive"))
    )
    (net (code "35") (name "/DI20") (class "Default")
      (node (ref "U2") (pin "52") (pinfunction "PC11_52") (pintype "passive"))
      (node (ref "X3.3") (pin "1") (pinfunction "P_1") (pintype "passive"))
    )
    (net (code "36") (name "/DI21") (class "Default")
      (node (ref "U2") (pin "36") (pinfunction "PB15_36") (pintype "passive"))
      (node (ref "X3.4") (pin "1") (pinfunction "P_1") (pintype "passive"))
    )
    (net (code "37") (name "/DI22") (class "Default")
      (node (ref "U2") (pin "35") (pinfunction "PB14_35") (pintype "passive"))
      (node (ref "X3.6") (pin "1") (pinfunction "P_1") (pintype "passive"))
    )
    (net (code "38") (name "/DI23") (class "Default")
      (node (ref "J2") (pin "7") (pinfunction "7_7") (pintype "bidirectional"))
      (node (ref "U2") (pin "42") (pinfunction "PA9_42") (pintype "passive"))
      (node (ref "X10.1") (pin "1") (pinfunction "P_1") (pintype "passive"))
    )
    (net (code "39") (name "/DI24") (class "Default")
      (node (ref "U1") (pin "9") (pinfunction "GPB7_9") (pintype "bidirectional"))
      (node (ref "X11.1") (pin "1") (pinfunction "P_1") (pintype "passive"))
    )
    (net (code "40") (name "/DO1") (class "Default")
      (node (ref "U2") (pin "15") (pinfunction "PA1_15") (pintype "passive"))
      (node (ref "X2.6") (pin "1") (pinfunction "P_1") (pintype "passive"))
    )
    (net (code "41") (name "/DO2") (class "Default")
      (node (ref "U2") (pin "14") (pinfunction "PA0_14") (pintype "passive"))
      (node (ref "X2.4") (pin "1") (pinfunction "P_1") (pintype "passive"))
    )
    (net (code "42") (name "/DO3") (class "Default")
      (node (ref "U2") (pin "10") (pinfunction "PC2_10") (pintype "passive"))
      (node (ref "X2.3") (pin "1") (pinfunction "P_1") (pintype "passive"))
    )
    (net (code "43") (name "/DO4") (class "Default")
      (node (ref "U2") (pin "11") (pinfunction "PC3_11") (pintype "passive"))
      (node (ref "X2.1") (pin "1") (pinfunction "P_1") (pintype "passive"))
    )
    (net (code "44") (name "/DO5") (class "Default")
      (node (ref "U2") (pin "9") (pinfunction "PC1_9") (pintype "passive"))
      (node (ref "X6.1") (pin "1") (pinfunction "P_1") (pintype "passive"))
    )
    (net (code "45") (name "/DO6") (class "Default")
      (node (ref "U2") (pin "8") (pinfunction "PC0_8") (pintype "passive"))
      (node (ref "X6.3") (pin "1") (pinfunction "P_1") (pintype "passive"))
    )
    (net (code "46") (name "/DO7") (class "Default")
      (node (ref "U2") (pin "6") (pinfunction "PH1-OSC_OUT_6") (pintype "passive"))
      (node (ref "X6.4") (pin "1") (pinfunction "P_1") (pintype "passive"))
    )
    (net (code "47") (name "/DO8") (class "Default")
      (node (ref "U2") (pin "5") (pinfunction "PH0-OSC_IN_5") (pintype "passive"))
      (node (ref "X6.6") (pin "1") (pinfunction "P_1") (pintype "passive"))
    )
    (net (code "48") (name "/DO9") (class "Default")
      (node (ref "U2") (pin "4") (pinfunction "PC15-OSC32_OUT_4") (pintype "passive"))
      (node (ref "X6.8") (pin "1") (pinfunction "P_1") (pintype "passive"))
    )
    (net (code "49") (name "/DO10") (class "Default")
      (node (ref "U2") (pin "3") (pinfunction "PC14-OSC32_IN_3") (pintype "passive"))
      (node (ref "X6.9") (pin "1") (pinfunction "P_1") (pintype "passive"))
    )
    (net (code "50") (name "/DO11") (class "Default")
      (node (ref "U2") (pin "2") (pinfunction "PC13_2") (pintype "passive"))
      (node (ref "X6.11") (pin "1") (pinfunction "P_1") (pintype "passive"))
    )
    (net (code "51") (name "/DO12") (class "Default")
      (node (ref "U1") (pin "23") (pinfunction "GPA6_23") (pintype "bidirectional"))
      (node (ref "X8.11") (pin "1") (pinfunction "P_1") (pintype "passive"))
    )
    (net (code "52") (name "/DO13") (class "Default")
      (node (ref "U1") (pin "22") (pinfunction "GPA5_22") (pintype "bidirectional"))
      (node (ref "X8.9") (pin "1") (pinfunction "P_1") (pintype "passive"))
    )
    (net (code "53") (name "/DO14") (class "Default")
      (node (ref "U1") (pin "21") (pinfunction "GPA4_21") (pintype "bidirectional"))
      (node (ref "X8.8") (pin "1") (pinfunction "P_1") (pintype "passive"))
    )
    (net (code "54") (name "/DO15") (class "Default")
      (node (ref "U1") (pin "20") (pinfunction "GPA3_20") (pintype "bidirectional"))
      (node (ref "X8.6") (pin "1") (pinfunction "P_1") (pintype "passive"))
    )
    (net (code "55") (name "/DO16") (class "Default")
      (node (ref "U1") (pin "19") (pinfunction "GPA2_19") (pintype "bidirectional"))
      (node (ref "X8.4") (pin "1") (pinfunction "P_1") (pintype "passive"))
    )
    (net (code "56") (name "/DO17") (class "Default")
      (node (ref "U1") (pin "18") (pinfunction "GPA1_18") (pintype "bidirectional"))
      (node (ref "X8.3") (pin "1") (pinfunction "P_1") (pintype "passive"))
    )
    (net (code "57") (name "/DO18") (class "Default")
      (node (ref "U1") (pin "17") (pinfunction "GPA0_17") (pintype "bidirectional"))
      (node (ref "X8.1") (pin "1") (pinfunction "P_1") (pintype "passive"))
    )
    (net (code "58") (name "/DO19") (class "Default")
      (node (ref "U2") (pin "57") (pinfunction "PB5_57") (pintype "passive"))
      (node (ref "X4.1") (pin "1") (pinfunction "P_1") (pintype "passive"))
    )
    (net (code "59") (name "/DO20") (class "Default")
      (node (ref "U2") (pin "56") (pinfunction "PB4_56") (pintype "passive"))
      (node (ref "X4.3") (pin "1") (pinfunction "P_1") (pintype "passive"))
    )
    (net (code "60") (name "/DO21") (class "Default")
      (node (ref "U2") (pin "54") (pinfunction "PB11_54") (pintype "passive"))
      (node (ref "X4.4") (pin "1") (pinfunction "P_1") (pintype "passive"))
    )
    (net (code "61") (name "/DO22") (class "Default")
      (node (ref "U2") (pin "53") (pinfunction "PC12_53") (pintype "passive"))
      (node (ref "X4.6") (pin "1") (pinfunction "P_1") (pintype "passive"))
    )
    (net (code "62") (name "/DO23") (class "Default")
      (node (ref "J2") (pin "9") (pinfunction "9_9") (pintype "bidirectional"))
      (node (ref "U2") (pin "43") (pinfunction "PA10_43") (pintype "passive"))
      (node (ref "X10.2") (pin "1") (pinfunction "P_1") (pintype "passive"))
    )
    (net (code "63") (name "/DO24") (class "Default")
      (node (ref "U1") (pin "24") (pinfunction "GPA7_24") (pintype "bidirectional"))
      (node (ref "X11.2") (pin "1") (pinfunction "P_1") (pintype "passive"))
    )
    (net (code "64") (name "/I2C_SCL") (class "Default")
      (node (ref "R4") (pin "1") (pinfunction "1_1") (pintype "passive"))
      (node (ref "U1") (pin "11") (pinfunction "SCL_11") (pintype "input"))
      (node (ref "U2") (pin "58") (pinfunction "PB6_58") (pintype "passive"))
    )
    (net (code "65") (name "/I2C_SDA") (class "Default")
      (node (ref "R3") (pin "1") (pinfunction "1_1") (pintype "passive"))
      (node (ref "U1") (pin "12") (pinfunction "SDA_12") (pintype "bidirectional"))
      (node (ref "U2") (pin "59") (pinfunction "PB7_59") (pintype "passive"))
    )
    (net (code "66") (name "/JTAG_JTDI") (class "Default")
      (node (ref "J2") (pin "8") (pinfunction "8_8") (pintype "bidirectional"))
      (node (ref "U2") (pin "50") (pinfunction "PA15_50") (pintype "passive"))
    )
    (net (code "67") (name "/JTAG_JTDO") (class "Default")
      (node (ref "J2") (pin "6") (pinfunction "6_6") (pintype "bidirectional"))
      (node (ref "U2") (pin "55") (pinfunction "PB3_55") (pintype "passive"))
    )
    (net (code "68") (name "/JTAG_NRST") (class "Default")
      (node (ref "J2") (pin "10") (pinfunction "10_10") (pintype "bidirectional"))
      (node (ref "U2") (pin "7") (pinfunction "NRST_7") (pintype "passive"))
    )
    (net (code "69") (name "/JTAG_SWCLK") (class "Default")
      (node (ref "J2") (pin "4") (pinfunction "4_4") (pintype "bidirectional"))
      (node (ref "U2") (pin "49") (pinfunction "PA14_49") (pintype "passive"))
    )
    (net (code "70") (name "/JTAG_SWDIO") (class "Default")
      (node (ref "J2") (pin "2") (pinfunction "2_2") (pintype "bidirectional"))
      (node (ref "U2") (pin "46") (pinfunction "PA13_46") (pintype "passive"))
    )
    (net (code "71") (name "/POTI1") (class "Default")
      (node (ref "X5.13") (pin "1") (pinfunction "P_1") (pintype "passive"))
      (node (ref "X6.13") (pin "1") (pinfunction "P_1") (pintype "passive"))
    )
    (net (code "72") (name "/POTI2") (class "Default")
      (node (ref "X7.13") (pin "1") (pinfunction "P_1") (pintype "passive"))
      (node (ref "X8.13") (pin "1") (pinfunction "P_1") (pintype "passive"))
    )
    (net (code "73") (name "/RJ12_CLK") (class "Default")
      (node (ref "J1") (pin "4") (pinfunction "4_4") (pintype "passive"))
      (node (ref "R7") (pin "1") (pinfunction "1_1") (pintype "passive"))
      (node (ref "U2") (pin "21") (pinfunction "PA5_21") (pintype "passive"))
      (node (ref "VD2") (pin "2") (pinfunction "A1_2") (pintype "passive"))
    )
    (net (code "74") (name "/RJ12_CS") (class "Default")
      (node (ref "J1") (pin "5") (pinfunction "5_5") (pintype "passive"))
      (node (ref "R6") (pin "1") (pinfunction "1_1") (pintype "passive"))
      (node (ref "U2") (pin "20") (pinfunction "PA4_20") (pintype "passive"))
      (node (ref "VD2") (pin "1") (pinfunction "A_1") (pintype "passive"))
    )
    (net (code "75") (name "/RJ12_MISO") (class "Default")
      (node (ref "J1") (pin "3") (pinfunction "3_3") (pintype "passive"))
      (node (ref "U2") (pin "22") (pinfunction "PA6_22") (pintype "passive"))
      (node (ref "VD1") (pin "1") (pinfunction "A_1") (pintype "passive"))
    )
    (net (code "76") (name "/RJ12_MOSI") (class "Default")
      (node (ref "J1") (pin "2") (pinfunction "2_2") (pintype "passive"))
      (node (ref "R8") (pin "1") (pinfunction "1_1") (pintype "passive"))
      (node (ref "U2") (pin "23") (pinfunction "PA7_23") (pintype "passive"))
      (node (ref "VD1") (pin "2") (pinfunction "A1_2") (pintype "passive"))
    )
    (net (code "77") (name "/VDDA") (class "Default")
      (node (ref "C10") (pin "1") (pinfunction "1_1") (pintype "passive"))
      (node (ref "C2") (pin "1") (pinfunction "1_1") (pintype "passive"))
      (node (ref "SJ1") (pin "2") (pinfunction "2_2") (pintype "passive"))
      (node (ref "U2") (pin "13") (pinfunction "VDDA/VREF+_2_13") (pintype "power_in"))
    )
    (net (code "78") (name "GND") (class "Default")
      (node (ref "C1") (pin "2") (pinfunction "2_2") (pintype "passive"))
      (node (ref "C10") (pin "2") (pinfunction "2_2") (pintype "passive"))
      (node (ref "C11") (pin "2") (pinfunction "2_2") (pintype "passive"))
      (node (ref "C12") (pin "2") (pinfunction "2_2") (pintype "passive"))
      (node (ref "C13") (pin "2") (pinfunction "2_2") (pintype "passive"))
      (node (ref "C15") (pin "2") (pinfunction "2_2") (pintype "passive"))
      (node (ref "C16") (pin "2") (pinfunction "2_2") (pintype "passive"))
      (node (ref "C2") (pin "2") (pinfunction "2_2") (pintype "passive"))
      (node (ref "C20") (pin "2") (pinfunction "2_2") (pintype "passive"))
      (node (ref "C3") (pin "2") (pinfunction "2_2") (pintype "passive"))
      (node (ref "C4") (pin "2") (pinfunction "2_2") (pintype "passive"))
      (node (ref "C5") (pin "2") (pinfunction "2_2") (pintype "passive"))
      (node (ref "C6") (pin "2") (pinfunction "2_2") (pintype "passive"))
      (node (ref "C7") (pin "2") (pinfunction "2_2") (pintype "passive"))
      (node (ref "C8") (pin "2") (pinfunction "2_2") (pintype "passive"))
      (node (ref "C9") (pin "2") (pinfunction "2_2") (pintype "passive"))
      (node (ref "H1") (pin "B3,0") (pinfunction "MOUNT_B3,0") (pintype "passive"))
      (node (ref "H2") (pin "B3,0") (pinfunction "MOUNT_B3,0") (pintype "passive"))
      (node (ref "H3") (pin "B3,0") (pinfunction "MOUNT_B3,0") (pintype "passive"))
      (node (ref "H4") (pin "B3,0") (pinfunction "MOUNT_B3,0") (pintype "passive"))
      (node (ref "IC1") (pin "6") (pinfunction "GND_6") (pintype "bidirectional"))
      (node (ref "IC2") (pin "1") (pinfunction "GND/ADJ_1") (pintype "input"))
      (node (ref "J1") (pin "6") (pinfunction "6_6") (pintype "passive"))
      (node (ref "J2") (pin "3") (pinfunction "3_3") (pintype "bidirectional"))
      (node (ref "J2") (pin "5") (pinfunction "5_5") (pintype "bidirectional"))
      (node (ref "LED1") (pin "C") (pinfunction "C_C") (pintype "passive"))
      (node (ref "R2") (pin "1") (pinfunction "1_1") (pintype "passive"))
      (node (ref "R5") (pin "1") (pinfunction "1_1") (pintype "passive"))
      (node (ref "R6") (pin "2") (pinfunction "2_2") (pintype "passive"))
      (node (ref "U1") (pin "1") (pinfunction "VSS_1") (pintype "power_in"))
      (node (ref "U1") (pin "13") (pinfunction "ADDR_13") (pintype "input"))
      (node (ref "U2") (pin "12") (pinfunction "VSSA/VREF-_2_12") (pintype "power_in"))
      (node (ref "U2") (pin "18") (pinfunction "VSS_2_18") (pintype "power_in"))
      (node (ref "U2") (pin "31") (pinfunction "VSSA/VREF-_31") (pintype "power_in"))
      (node (ref "U2") (pin "47") (pinfunction "VSS_3_47") (pintype "power_in"))
      (node (ref "U2") (pin "63") (pinfunction "VSS_63") (pintype "power_in"))
      (node (ref "VD1") (pin "3") (pinfunction "C_3") (pintype "passive"))
      (node (ref "VD2") (pin "3") (pinfunction "C_3") (pintype "passive"))
      (node (ref "X1.10") (pin "1") (pinfunction "P_1") (pintype "passive"))
      (node (ref "X1.2") (pin "1") (pinfunction "P_1") (pintype "passive"))
      (node (ref "X1.5") (pin "1") (pinfunction "P_1") (pintype "passive"))
      (node (ref "X1.7") (pin "1") (pinfunction "P_1") (pintype "passive"))
      (node (ref "X2.10") (pin "1") (pinfunction "P_1") (pintype "passive"))
      (node (ref "X2.2") (pin "1") (pinfunction "P_1") (pintype "passive"))
      (node (ref "X2.5") (pin "1") (pinfunction "P_1") (pintype "passive"))
      (node (ref "X2.7") (pin "1") (pinfunction "P_1") (pintype "passive"))
      (node (ref "X3.10") (pin "1") (pinfunction "P_1") (pintype "passive"))
      (node (ref "X3.2") (pin "1") (pinfunction "P_1") (pintype "passive"))
      (node (ref "X3.5") (pin "1") (pinfunction "P_1") (pintype "passive"))
      (node (ref "X3.7") (pin "1") (pinfunction "P_1") (pintype "passive"))
      (node (ref "X4.10") (pin "1") (pinfunction "P_1") (pintype "passive"))
      (node (ref "X4.2") (pin "1") (pinfunction "P_1") (pintype "passive"))
      (node (ref "X4.5") (pin "1") (pinfunction "P_1") (pintype "passive"))
      (node (ref "X4.7") (pin "1") (pinfunction "P_1") (pintype "passive"))
      (node (ref "X5.10") (pin "1") (pinfunction "P_1") (pintype "passive"))
      (node (ref "X5.14") (pin "1") (pinfunction "P_1") (pintype "passive"))
      (node (ref "X5.16") (pin "1") (pinfunction "P_1") (pintype "passive"))
      (node (ref "X5.18") (pin "1") (pinfunction "P_1") (pintype "passive"))
      (node (ref "X5.2") (pin "1") (pinfunction "P_1") (pintype "passive"))
      (node (ref "X5.5") (pin "1") (pinfunction "P_1") (pintype "passive"))
      (node (ref "X5.7") (pin "1") (pinfunction "P_1") (pintype "passive"))
      (node (ref "X6.10") (pin "1") (pinfunction "P_1") (pintype "passive"))
      (node (ref "X6.14") (pin "1") (pinfunction "P_1") (pintype "passive"))
      (node (ref "X6.2") (pin "1") (pinfunction "P_1") (pintype "passive"))
      (node (ref "X6.5") (pin "1") (pinfunction "P_1") (pintype "passive"))
      (node (ref "X6.7") (pin "1") (pinfunction "P_1") (pintype "passive"))
      (node (ref "X7.10") (pin "1") (pinfunction "P_1") (pintype "passive"))
      (node (ref "X7.14") (pin "1") (pinfunction "P_1") (pintype "passive"))
      (node (ref "X7.2") (pin "1") (pinfunction "P_1") (pintype "passive"))
      (node (ref "X7.5") (pin "1") (pinfunction "P_1") (pintype "passive"))
      (node (ref "X7.7") (pin "1") (pinfunction "P_1") (pintype "passive"))
      (node (ref "X8.10") (pin "1") (pinfunction "P_1") (pintype "passive"))
      (node (ref "X8.14") (pin "1") (pinfunction "P_1") (pintype "passive"))
      (node (ref "X8.2") (pin "1") (pinfunction "P_1") (pintype "passive"))
      (node (ref "X8.5") (pin "1") (pinfunction "P_1") (pintype "passive"))
      (node (ref "X8.7") (pin "1") (pinfunction "P_1") (pintype "passive"))
      (node (ref "X9.2") (pin "1") (pinfunction "P_1") (pintype "passive"))
    )
    (net (code "79") (name "Net-(LED1-PadA)") (class "Default")
      (node (ref "LED1") (pin "A") (pinfunction "A_A") (pintype "passive"))
      (node (ref "R10") (pin "1") (pinfunction "1_1") (pintype "passive"))
    )
    (net (code "80") (name "Net-(U1-~{RESET})") (class "Default")
      (node (ref "R1") (pin "1") (pinfunction "1_1") (pintype "passive"))
      (node (ref "U1") (pin "14") (pinfunction "~{RESET}_14") (pintype "input"))
    )
    (net (code "81") (name "Net-(U2-VCAP_1)") (class "Default")
      (node (ref "C20") (pin "1") (pinfunction "1_1") (pintype "passive"))
      (node (ref "U2") (pin "30") (pinfunction "VCAP_1_30") (pintype "power_in"))
    )
    (net (code "82") (name "V+") (class "Default")
      (node (ref "C4") (pin "1") (pinfunction "1_1") (pintype "passive"))
      (node (ref "IC1") (pin "7") (pinfunction "VREFIN_7") (pintype "bidirectional"))
      (node (ref "SJ1") (pin "1") (pinfunction "1_1") (pintype "passive"))
      (node (ref "X1.12") (pin "1") (pinfunction "P_1") (pintype "passive"))
      (node (ref "X1.9") (pin "1") (pinfunction "P_1") (pintype "passive"))
      (node (ref "X2.12") (pin "1") (pinfunction "P_1") (pintype "passive"))
      (node (ref "X2.9") (pin "1") (pinfunction "P_1") (pintype "passive"))
      (node (ref "X3.12") (pin "1") (pinfunction "P_1") (pintype "passive"))
      (node (ref "X3.9") (pin "1") (pinfunction "P_1") (pintype "passive"))
      (node (ref "X4.12") (pin "1") (pinfunction "P_1") (pintype "passive"))
      (node (ref "X4.9") (pin "1") (pinfunction "P_1") (pintype "passive"))
      (node (ref "X5.12") (pin "1") (pinfunction "P_1") (pintype "passive"))
      (node (ref "X6.12") (pin "1") (pinfunction "P_1") (pintype "passive"))
      (node (ref "X7.12") (pin "1") (pinfunction "P_1") (pintype "passive"))
      (node (ref "X8.12") (pin "1") (pinfunction "P_1") (pintype "passive"))
    )
    (net (code "83") (name "unconnected-(U1-INTA-Pad16)") (class "Default")
      (node (ref "U1") (pin "16") (pinfunction "INTA_16") (pintype "output"))
    )
    (net (code "84") (name "unconnected-(U1-INTB-Pad15)") (class "Default")
      (node (ref "U1") (pin "15") (pinfunction "INTB_15") (pintype "output"))
    )
  )
)
